# 02_ECE453-Digital-Interface.net
KiCad netlist of a schematic drawn in Altium Designer
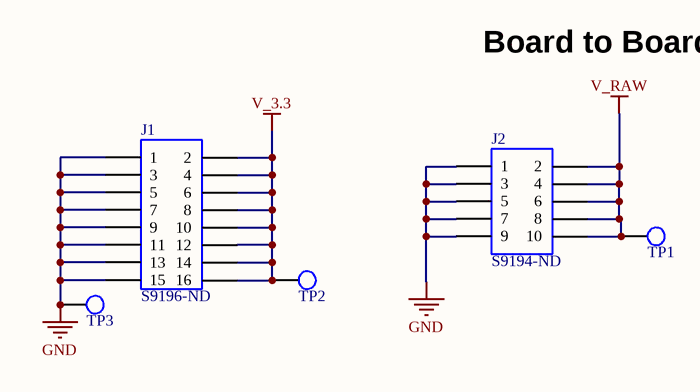
[diagram p0: 02 ECE453-Digital-Interface.SchDoc]

(export (version "E")
  (design (tool "Eeschema 10.0.6"))
  (components
    (comp (ref "J1")
      (value "SFH11-PBPC-D08-ST-BK")
      (footprint "SFH11-PBPC-D08-ST-BK")
      (description "CONN HDR 10POS 0.1 GOLD PCB")
      (fields (field (name "SUPPLIER PART NUMBER 1") "S9196-ND"))
      (libsource (lib "Connectors") (part "SFH11-PBPC-D08-ST-BK"))
    )
    (comp (ref "J2")
      (value "SFH11-PBPC-D05-ST-BK")
      (footprint "SFH11-PBPC-D05-ST-BK")
      (description "CONN HDR 10POS 0.1 GOLD PCB")
      (fields (field (name "SUPPLIER PART NUMBER 1") "S9194-ND"))
      (libsource (lib "Connectors") (part "SFH11-PBPC-D05-ST-BK"))
    )
    (comp (ref "TP1")
      (value "TP_1206")
      (footprint "TP-SMC-1206")
      (description "Test Point SMD 1206")
      (libsource (lib "ECE453_PWR") (part "TP_1206"))
    )
    (comp (ref "TP2")
      (value "TP_1206")
      (footprint "TP-SMC-1206")
      (description "Test Point SMD 1206")
      (libsource (lib "ECE453_PWR") (part "TP_1206"))
    )
    (comp (ref "TP3")
      (value "TP_1206")
      (footprint "TP-SMC-1206")
      (description "Test Point SMD 1206")
      (libsource (lib "ECE453_PWR") (part "TP_1206"))
    )
  )
  (nets
    (net (code "1") (name "GND") (class "Default")
      (node (ref "J1") (pin "1") (pinfunction "1_1") (pintype "passive"))
      (node (ref "J1") (pin "11") (pinfunction "11_11") (pintype "passive"))
      (node (ref "J1") (pin "13") (pinfunction "13_13") (pintype "passive"))
      (node (ref "J1") (pin "15") (pinfunction "15_15") (pintype "passive"))
      (node (ref "J1") (pin "3") (pinfunction "3_3") (pintype "passive"))
      (node (ref "J1") (pin "5") (pinfunction "5_5") (pintype "passive"))
      (node (ref "J1") (pin "7") (pinfunction "7_7") (pintype "passive"))
      (node (ref "J1") (pin "9") (pinfunction "9_9") (pintype "passive"))
      (node (ref "J2") (pin "1") (pinfunction "1_1") (pintype "passive"))
      (node (ref "J2") (pin "3") (pinfunction "3_3") (pintype "passive"))
      (node (ref "J2") (pin "5") (pinfunction "5_5") (pintype "passive"))
      (node (ref "J2") (pin "7") (pinfunction "7_7") (pintype "passive"))
      (node (ref "J2") (pin "9") (pinfunction "9_9") (pintype "passive"))
      (node (ref "TP3") (pin "1") (pintype "passive"))
    )
    (net (code "2") (name "V_3.3") (class "Default")
      (node (ref "J1") (pin "10") (pinfunction "10_10") (pintype "passive"))
      (node (ref "J1") (pin "12") (pinfunction "12_12") (pintype "passive"))
      (node (ref "J1") (pin "14") (pinfunction "14_14") (pintype "passive"))
      (node (ref "J1") (pin "16") (pinfunction "16_16") (pintype "passive"))
      (node (ref "J1") (pin "2") (pinfunction "2_2") (pintype "passive"))
      (node (ref "J1") (pin "4") (pinfunction "4_4") (pintype "passive"))
      (node (ref "J1") (pin "6") (pinfunction "6_6") (pintype "passive"))
      (node (ref "J1") (pin "8") (pinfunction "8_8") (pintype "passive"))
      (node (ref "TP2") (pin "1") (pintype "passive"))
    )
    (net (code "3") (name "V_RAW") (class "Default")
      (node (ref "J2") (pin "10") (pinfunction "10_10") (pintype "passive"))
      (node (ref "J2") (pin "2") (pinfunction "2_2") (pintype "passive"))
      (node (ref "J2") (pin "4") (pinfunction "4_4") (pintype "passive"))
      (node (ref "J2") (pin "6") (pinfunction "6_6") (pintype "passive"))
      (node (ref "J2") (pin "8") (pinfunction "8_8") (pintype "passive"))
      (node (ref "TP1") (pin "1") (pintype "passive"))
    )
  )
)
